# Adafruit_MONSTER_M4SK.net
KiCad netlist of a schematic drawn in EAGLE
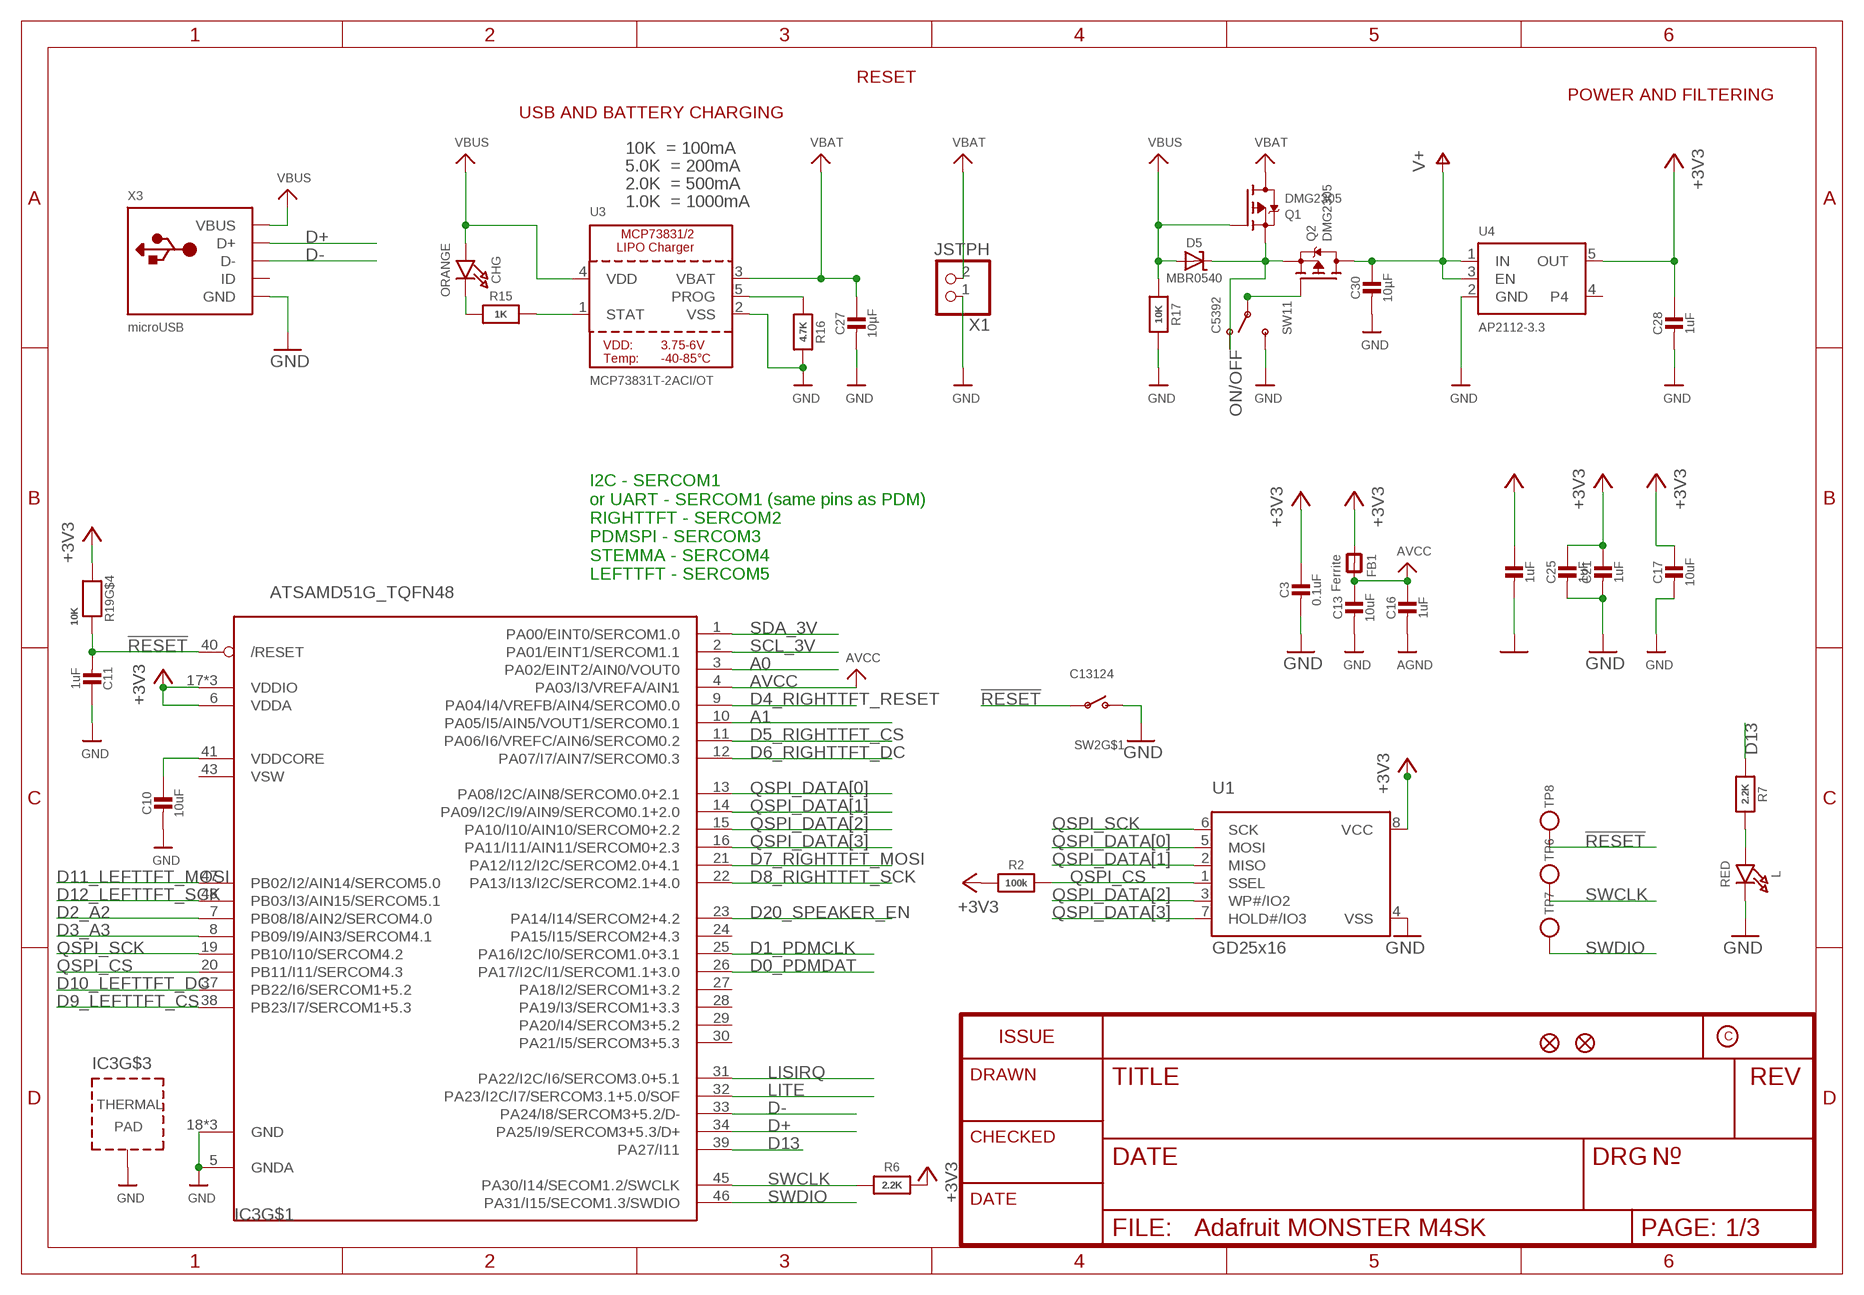
[diagram p0: schematic, sheet 1]
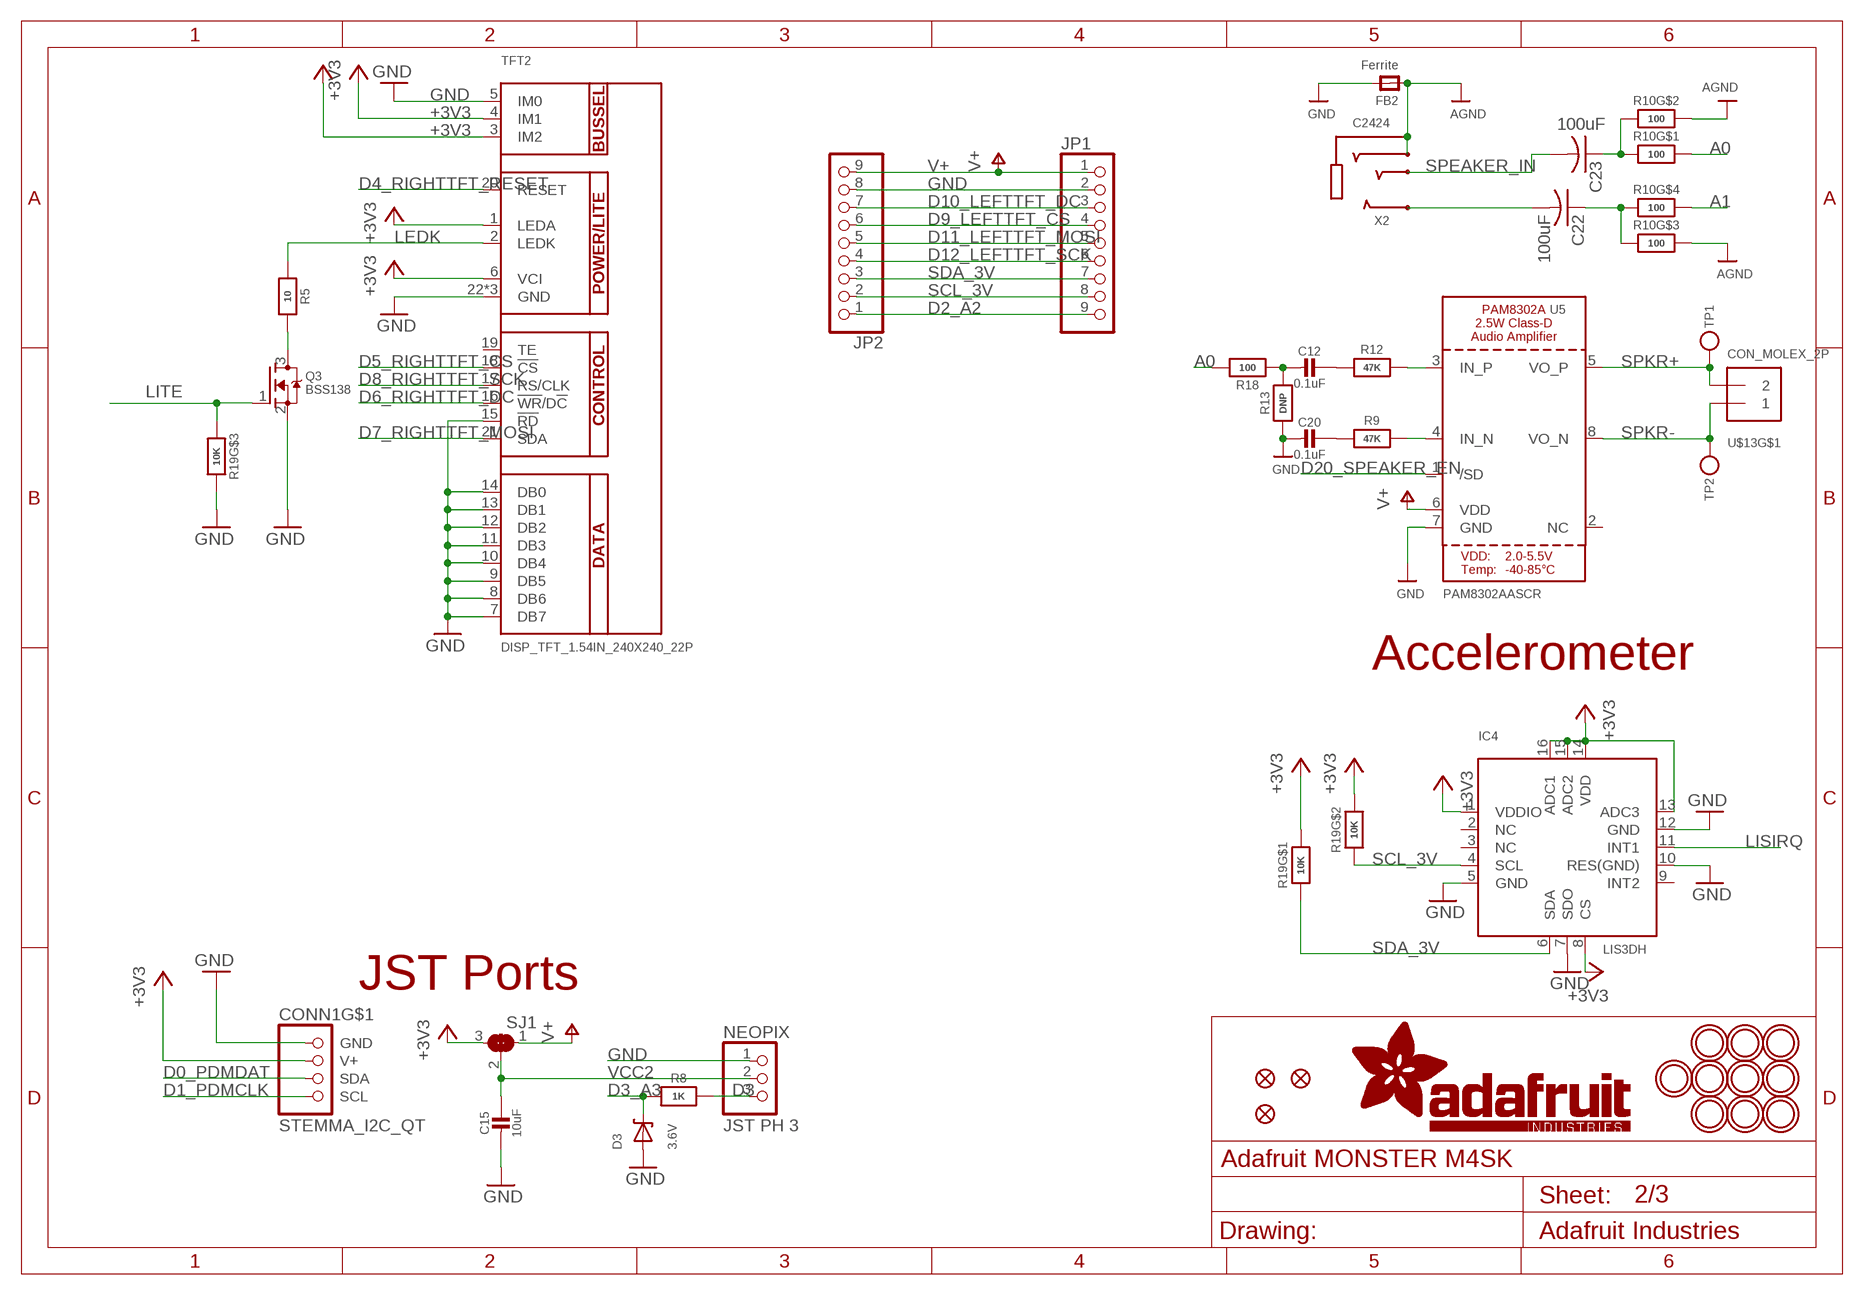
[diagram p1: schematic, sheet 2]
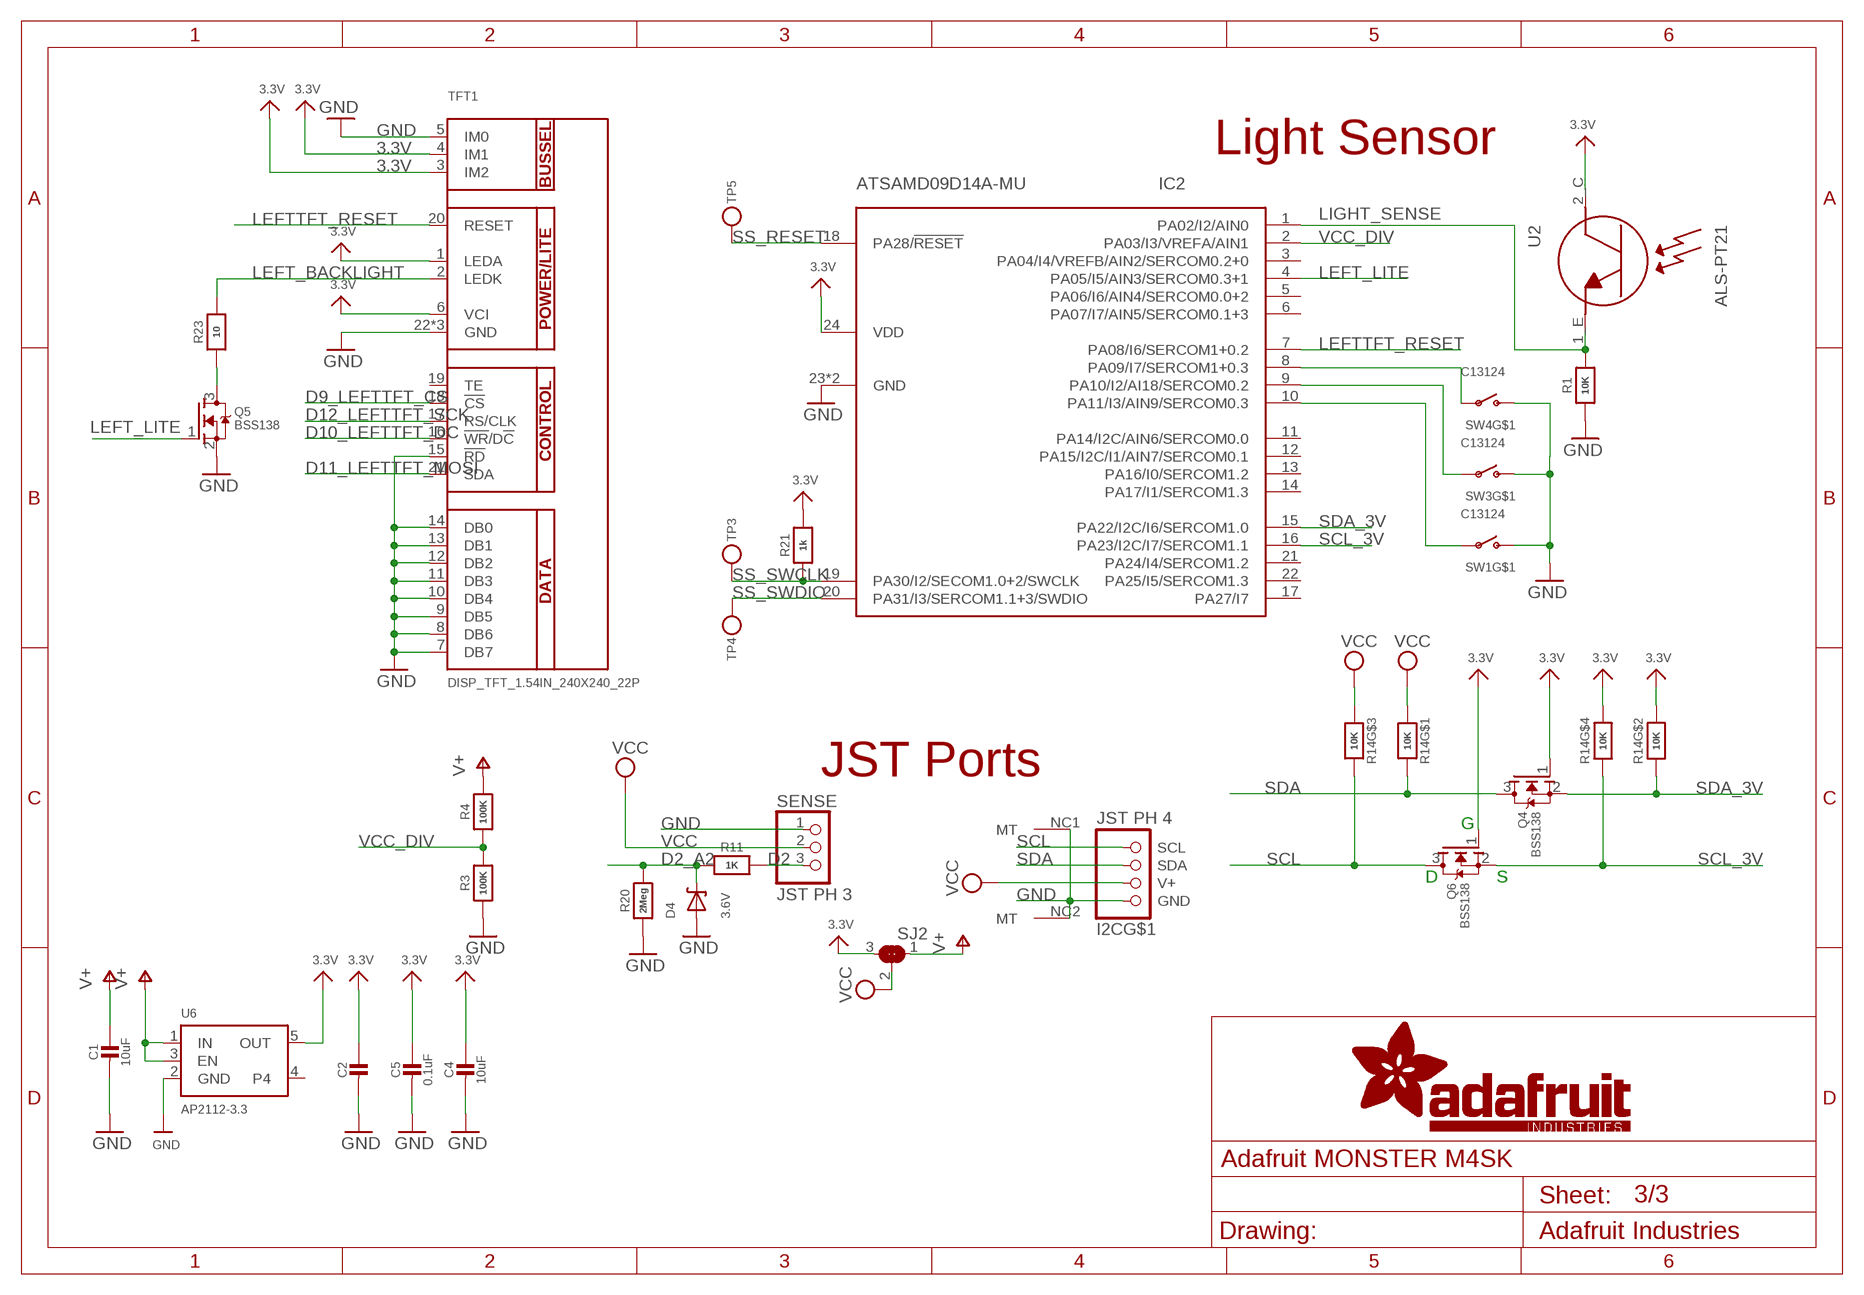
[diagram p2: schematic, sheet 3]

(export (version "E")
  (design (tool "Eeschema 10.0.6"))
  (components
    (comp (ref "C3")
      (value "0.1uF")
      (footprint "eagle-import:0603-NO")
      (libsource (lib "eagle-import") (part "CAP_CERAMIC0603_NO"))
    )
    (comp (ref "C10")
      (value "10uF")
      (footprint "eagle-import:_0805MP")
      (libsource (lib "eagle-import") (part "CAP_CERAMIC_0805MP"))
    )
    (comp (ref "C11")
      (value "1uF")
      (footprint "eagle-import:0603-NO")
      (libsource (lib "eagle-import") (part "CAP_CERAMIC0603_NO"))
    )
    (comp (ref "C13")
      (value "10uF")
      (footprint "eagle-import:0805-NO")
      (libsource (lib "eagle-import") (part "CAP_CERAMIC0805-NOOUTLINE"))
    )
    (comp (ref "C16")
      (value "1uF")
      (footprint "eagle-import:0603-NO")
      (libsource (lib "eagle-import") (part "CAP_CERAMIC0603_NO"))
    )
    (comp (ref "C17")
      (value "10uF")
      (footprint "eagle-import:0805-NO")
      (libsource (lib "eagle-import") (part "CAP_CERAMIC0805-NOOUTLINE"))
    )
    (comp (ref "C19")
      (value "1uF")
      (footprint "eagle-import:0603-NO")
      (libsource (lib "eagle-import") (part "CAP_CERAMIC0603_NO"))
    )
    (comp (ref "C21")
      (value "1uF")
      (footprint "eagle-import:0603-NO")
      (libsource (lib "eagle-import") (part "CAP_CERAMIC0603_NO"))
    )
    (comp (ref "C25")
      (value "1uF")
      (footprint "eagle-import:0603-NO")
      (libsource (lib "eagle-import") (part "CAP_CERAMIC0603_NO"))
    )
    (comp (ref "C27")
      (value "10µF")
      (footprint "eagle-import:0805-NO")
      (libsource (lib "eagle-import") (part "CAP_CERAMIC0805-NOOUTLINE"))
    )
    (comp (ref "C28")
      (value "1uF")
      (footprint "eagle-import:0603-NO")
      (libsource (lib "eagle-import") (part "CAP_CERAMIC0603_NO"))
    )
    (comp (ref "C30")
      (value "10µF")
      (footprint "eagle-import:0805-NO")
      (libsource (lib "eagle-import") (part "CAP_CERAMIC0805-NOOUTLINE"))
    )
    (comp (ref "CHG")
      (value "ORANGE")
      (footprint "eagle-import:CHIPLED_0805_NOOUTLINE")
      (libsource (lib "eagle-import") (part "LED0805_NOOUTLINE"))
    )
    (comp (ref "D5")
      (value "MBR0540")
      (footprint "eagle-import:SOD-123")
      (libsource (lib "eagle-import") (part "DIODE-SCHOTTKYSOD-123"))
    )
    (comp (ref "FB1")
      (value "Ferrite")
      (footprint "eagle-import:0805-NO")
      (libsource (lib "eagle-import") (part "FERRITE-0805NO"))
    )
    (comp (ref "IC3")
      (value "ATSAMD51G_TQFN48")
      (footprint "eagle-import:TQFN48_7MM")
      (libsource (lib "eagle-import") (part "ATSAMD51G_TQFN48"))
    )
    (comp (ref "L")
      (value "RED")
      (footprint "eagle-import:CHIPLED_0805_NOOUTLINE")
      (libsource (lib "eagle-import") (part "LED0805_NOOUTLINE"))
    )
    (comp (ref "Q1")
      (value "DMG2305")
      (footprint "eagle-import:SOT23-R")
      (libsource (lib "eagle-import") (part "MOSFET-P"))
    )
    (comp (ref "Q2")
      (value "DMG2305")
      (footprint "eagle-import:SOT23-R")
      (libsource (lib "eagle-import") (part "MOSFET-P"))
    )
    (comp (ref "R2")
      (value "100k")
      (footprint "eagle-import:0603-NO")
      (libsource (lib "eagle-import") (part "RESISTOR_0603_NOOUT"))
    )
    (comp (ref "R6")
      (value "2.2K")
      (footprint "eagle-import:0603-NO")
      (libsource (lib "eagle-import") (part "RESISTOR_0603_NOOUT"))
    )
    (comp (ref "R7")
      (value "2.2K")
      (footprint "eagle-import:0603-NO")
      (libsource (lib "eagle-import") (part "RESISTOR_0603_NOOUT"))
    )
    (comp (ref "R15")
      (value "1K")
      (footprint "eagle-import:0603-NO")
      (libsource (lib "eagle-import") (part "RESISTOR_0603_NOOUT"))
    )
    (comp (ref "R16")
      (value "4.7K")
      (footprint "eagle-import:0603-NO")
      (libsource (lib "eagle-import") (part "RESISTOR_0603_NOOUT"))
    )
    (comp (ref "R17")
      (value "10K")
      (footprint "eagle-import:0603-NO")
      (libsource (lib "eagle-import") (part "RESISTOR_0603_NOOUT"))
    )
    (comp (ref "R19")
      (value "10K")
      (footprint "eagle-import:RESPACK_4X0603")
      (libsource (lib "eagle-import") (part "RESISTOR_4PACK"))
    )
    (comp (ref "SW2")
      (value "C13124")
      (footprint "eagle-import:SPST_TACTILE_RA")
      (libsource (lib "eagle-import") (part "SWITCH_SPST_TACT_RA"))
    )
    (comp (ref "SW11")
      (value "C5392")
      (footprint "eagle-import:SPDT_SMT_SSSS811101")
      (libsource (lib "eagle-import") (part "SWITCH_SPDT"))
    )
    (comp (ref "TP6")
      (value "TESTPOINTROUND2MMNO")
      (footprint "eagle-import:TESTPOINT_ROUND_2MM_NO")
      (libsource (lib "eagle-import") (part "TESTPOINTROUND2MMNO"))
    )
    (comp (ref "TP7")
      (value "TESTPOINTROUND2MMNO")
      (footprint "eagle-import:TESTPOINT_ROUND_2MM_NO")
      (libsource (lib "eagle-import") (part "TESTPOINTROUND2MMNO"))
    )
    (comp (ref "TP8")
      (value "TESTPOINTROUND2MMNO")
      (footprint "eagle-import:TESTPOINT_ROUND_2MM_NO")
      (libsource (lib "eagle-import") (part "TESTPOINTROUND2MMNO"))
    )
    (comp (ref "U$34")
      (value "FIDUCIAL_1MM")
      (footprint "eagle-import:FIDUCIAL_1MM")
      (libsource (lib "eagle-import") (part "FIDUCIAL_1MM"))
    )
    (comp (ref "U$35")
      (value "FIDUCIAL_1MM")
      (footprint "eagle-import:FIDUCIAL_1MM")
      (libsource (lib "eagle-import") (part "FIDUCIAL_1MM"))
    )
    (comp (ref "U1")
      (value "GD25x16")
      (footprint "eagle-import:SOIC8_208MIL")
      (libsource (lib "eagle-import") (part "SPIFLASH_8PIN208MIL"))
    )
    (comp (ref "U3")
      (value "MCP73831T-2ACI/OT")
      (footprint "eagle-import:SOT23-5")
      (libsource (lib "eagle-import") (part "MCP73831/2"))
    )
    (comp (ref "U4")
      (value "AP2112-3.3")
      (footprint "eagle-import:SOT23-5")
      (libsource (lib "eagle-import") (part "VREG_SOT23-5"))
    )
    (comp (ref "X1")
      (value "JSTPH")
      (footprint "eagle-import:JSTPH2")
      (libsource (lib "eagle-import") (part "CON_JST_PH_2PIN"))
    )
    (comp (ref "X3")
      (value "microUSB")
      (footprint "eagle-import:4UCONN_20329_NARROW")
      (libsource (lib "eagle-import") (part "USB_MICRO_NARROW"))
    )
    (comp (ref "C12")
      (value "0.1uF")
      (footprint "eagle-import:0603-NO")
      (libsource (lib "eagle-import") (part "CAP_CERAMIC0603_NO"))
    )
    (comp (ref "C15")
      (value "10uF")
      (footprint "eagle-import:0805-NO")
      (libsource (lib "eagle-import") (part "CAP_CERAMIC0805-NOOUTLINE"))
    )
    (comp (ref "C20")
      (value "0.1uF")
      (footprint "eagle-import:0603-NO")
      (libsource (lib "eagle-import") (part "CAP_CERAMIC0603_NO"))
    )
    (comp (ref "C22")
      (value "100uF")
      (footprint "eagle-import:C1210")
      (libsource (lib "eagle-import") (part "C-USC1210"))
    )
    (comp (ref "C23")
      (value "100uF")
      (footprint "eagle-import:C1210")
      (libsource (lib "eagle-import") (part "C-USC1210"))
    )
    (comp (ref "CONN1")
      (value "STEMMA_I2C_QT")
      (footprint "eagle-import:JST_SH4")
      (libsource (lib "eagle-import") (part "STEMMA_I2C_QT"))
    )
    (comp (ref "D3")
      (value "3.6V")
      (footprint "eagle-import:SOD-323")
      (libsource (lib "eagle-import") (part "DIODE-ZENERSOD323"))
    )
    (comp (ref "FB2")
      (value "Ferrite")
      (footprint "eagle-import:_0805MP")
      (libsource (lib "eagle-import") (part "FERRITE_0805MP"))
    )
    (comp (ref "IC4")
      (value "LIS3DH")
      (footprint "eagle-import:LGA16_3X3MM")
      (libsource (lib "eagle-import") (part "ACCEL_LIS3DHTR"))
    )
    (comp (ref "JP1")
      (value "HEADER-1X9_JSTSH")
      (footprint "eagle-import:JST_SH9")
      (libsource (lib "eagle-import") (part "HEADER-1X9_JSTSH"))
    )
    (comp (ref "JP2")
      (value "HEADER-1X9_JSTSH")
      (footprint "eagle-import:JST_SH9")
      (libsource (lib "eagle-import") (part "HEADER-1X9_JSTSH"))
    )
    (comp (ref "NEOPIX")
      (value "JST PH 3")
      (footprint "eagle-import:JSTPH3")
      (libsource (lib "eagle-import") (part "CON_JST_PH_3PIN"))
    )
    (comp (ref "Q3")
      (value "BSS138")
      (footprint "eagle-import:SOT23-WIDE")
      (libsource (lib "eagle-import") (part "MOSFET-NWIDE"))
    )
    (comp (ref "R5")
      (value "10")
      (footprint "eagle-import:0603-NO")
      (libsource (lib "eagle-import") (part "RESISTOR_0603_NOOUT"))
    )
    (comp (ref "R8")
      (value "1K")
      (footprint "eagle-import:0603-NO")
      (libsource (lib "eagle-import") (part "RESISTOR_0603_NOOUT"))
    )
    (comp (ref "R9")
      (value "47K")
      (footprint "eagle-import:0603-NO")
      (libsource (lib "eagle-import") (part "RESISTOR_0603_NOOUT"))
    )
    (comp (ref "R10")
      (value "100")
      (footprint "eagle-import:RESPACK_4X0603")
      (libsource (lib "eagle-import") (part "RESISTOR_4PACK"))
    )
    (comp (ref "R12")
      (value "47K")
      (footprint "eagle-import:0603-NO")
      (libsource (lib "eagle-import") (part "RESISTOR_0603_NOOUT"))
    )
    (comp (ref "R13")
      (value "DNP")
      (footprint "eagle-import:0603-NO")
      (libsource (lib "eagle-import") (part "RESISTOR_0603_NOOUT"))
    )
    (comp (ref "R18")
      (value "100")
      (footprint "eagle-import:0603-NO")
      (libsource (lib "eagle-import") (part "RESISTOR_0603_NOOUT"))
    )
    (comp (ref "SJ1")
      (value "SOLDERJUMPER_2WAY")
      (footprint "eagle-import:SOLDERJUMPER_2WAY_OPEN_NOPASTE")
      (libsource (lib "eagle-import") (part "SOLDERJUMPER_2WAY"))
    )
    (comp (ref "TFT2")
      (value "DISP_TFT_1.54IN_240X240_22P")
      (footprint "eagle-import:TFT_1.54IN_240X240_22PIN")
      (libsource (lib "eagle-import") (part "DISP_TFT_1.54IN_240X240_22P"))
    )
    (comp (ref "TP1")
      (value "TESTPOINTROUND1.5MMNO")
      (footprint "eagle-import:TESTPOINT_ROUND_1.5MM_NO")
      (libsource (lib "eagle-import") (part "TESTPOINTROUND1.5MMNO"))
    )
    (comp (ref "TP2")
      (value "TESTPOINTROUND1.5MMNO")
      (footprint "eagle-import:TESTPOINT_ROUND_1.5MM_NO")
      (libsource (lib "eagle-import") (part "TESTPOINTROUND1.5MMNO"))
    )
    (comp (ref "U$3")
      (value "FIDUCIAL_1MM")
      (footprint "eagle-import:FIDUCIAL_1MM")
      (libsource (lib "eagle-import") (part "FIDUCIAL_1MM"))
    )
    (comp (ref "U$4")
      (value "FIDUCIAL_1MM")
      (footprint "eagle-import:FIDUCIAL_1MM")
      (libsource (lib "eagle-import") (part "FIDUCIAL_1MM"))
    )
    (comp (ref "U$5")
      (value "FIDUCIAL_1MM")
      (footprint "eagle-import:FIDUCIAL_1MM")
      (libsource (lib "eagle-import") (part "FIDUCIAL_1MM"))
    )
    (comp (ref "U$7")
      (value "MOUNTINGHOLE3.0THIN")
      (footprint "eagle-import:MOUNTINGHOLE_3.0_PLATEDTHIN")
      (libsource (lib "eagle-import") (part "MOUNTINGHOLE3.0THIN"))
    )
    (comp (ref "U$8")
      (value "MOUNTINGHOLE3.0THIN")
      (footprint "eagle-import:MOUNTINGHOLE_3.0_PLATEDTHIN")
      (libsource (lib "eagle-import") (part "MOUNTINGHOLE3.0THIN"))
    )
    (comp (ref "U$9")
      (value "MOUNTINGHOLE3.0THIN")
      (footprint "eagle-import:MOUNTINGHOLE_3.0_PLATEDTHIN")
      (libsource (lib "eagle-import") (part "MOUNTINGHOLE3.0THIN"))
    )
    (comp (ref "U$10")
      (value "MOUNTINGHOLE3.0THIN")
      (footprint "eagle-import:MOUNTINGHOLE_3.0_PLATEDTHIN")
      (libsource (lib "eagle-import") (part "MOUNTINGHOLE3.0THIN"))
    )
    (comp (ref "U$13")
      (value "CON_MOLEX_2P")
      (footprint "eagle-import:53398-0271")
      (libsource (lib "eagle-import") (part "CON_MOLEX_2P"))
    )
    (comp (ref "U$58")
      (value "MOUNTINGHOLE3.0THIN")
      (footprint "eagle-import:MOUNTINGHOLE_3.0_PLATEDTHIN")
      (libsource (lib "eagle-import") (part "MOUNTINGHOLE3.0THIN"))
    )
    (comp (ref "U$59")
      (value "MOUNTINGHOLE3.0THIN")
      (footprint "eagle-import:MOUNTINGHOLE_3.0_PLATEDTHIN")
      (libsource (lib "eagle-import") (part "MOUNTINGHOLE3.0THIN"))
    )
    (comp (ref "U$60")
      (value "MOUNTINGHOLE3.0THIN")
      (footprint "eagle-import:MOUNTINGHOLE_3.0_PLATEDTHIN")
      (libsource (lib "eagle-import") (part "MOUNTINGHOLE3.0THIN"))
    )
    (comp (ref "U$61")
      (value "MOUNTINGHOLE3.0THIN")
      (footprint "eagle-import:MOUNTINGHOLE_3.0_PLATEDTHIN")
      (libsource (lib "eagle-import") (part "MOUNTINGHOLE3.0THIN"))
    )
    (comp (ref "U$63")
      (value "MOUNTINGHOLE3.0THIN")
      (footprint "eagle-import:MOUNTINGHOLE_3.0_PLATEDTHIN")
      (libsource (lib "eagle-import") (part "MOUNTINGHOLE3.0THIN"))
    )
    (comp (ref "U$64")
      (value "MOUNTINGHOLE3.0THIN")
      (footprint "eagle-import:MOUNTINGHOLE_3.0_PLATEDTHIN")
      (libsource (lib "eagle-import") (part "MOUNTINGHOLE3.0THIN"))
    )
    (comp (ref "U5")
      (value "PAM8302AASCR")
      (footprint "eagle-import:MSOP8_0.65MM")
      (libsource (lib "eagle-import") (part "AUDIOAMP_PAM8302A"))
    )
    (comp (ref "X2")
      (value "C2424")
      (footprint "eagle-import:4UCONN_18510")
      (libsource (lib "eagle-import") (part "AUDIO_3.5MMJACK_4POL"))
    )
    (comp (ref "C1")
      (value "10uF")
      (footprint "eagle-import:0805-NO")
      (libsource (lib "eagle-import") (part "CAP_CERAMIC0805-NOOUTLINE"))
    )
    (comp (ref "C2")
      (value "10uF")
      (footprint "eagle-import:0805-NO")
      (libsource (lib "eagle-import") (part "CAP_CERAMIC0805-NOOUTLINE"))
    )
    (comp (ref "C4")
      (value "10uF")
      (footprint "eagle-import:0805-NO")
      (libsource (lib "eagle-import") (part "CAP_CERAMIC0805-NOOUTLINE"))
    )
    (comp (ref "C5")
      (value "0.1uF")
      (footprint "eagle-import:0603-NO")
      (libsource (lib "eagle-import") (part "CAP_CERAMIC0603_NO"))
    )
    (comp (ref "D4")
      (value "3.6V")
      (footprint "eagle-import:SOD-323")
      (libsource (lib "eagle-import") (part "DIODE-ZENERSOD323"))
    )
    (comp (ref "I2C")
      (value "JST PH 4")
      (footprint "eagle-import:JSTPH4")
      (libsource (lib "eagle-import") (part "STEMMA_I2C_RASMT"))
    )
    (comp (ref "IC2")
      (value "ATSAMD09D14A-MU")
      (footprint "eagle-import:QFN24_4MM")
      (libsource (lib "eagle-import") (part "ATSAMD09D14A-MU"))
    )
    (comp (ref "Q4")
      (value "BSS138")
      (footprint "eagle-import:SOT23-WIDE")
      (libsource (lib "eagle-import") (part "MOSFET-NWIDE"))
    )
    (comp (ref "Q5")
      (value "BSS138")
      (footprint "eagle-import:SOT23-WIDE")
      (libsource (lib "eagle-import") (part "MOSFET-NWIDE"))
    )
    (comp (ref "Q6")
      (value "BSS138")
      (footprint "eagle-import:SOT23-WIDE")
      (libsource (lib "eagle-import") (part "MOSFET-NWIDE"))
    )
    (comp (ref "R1")
      (value "10K")
      (footprint "eagle-import:0603-NO")
      (libsource (lib "eagle-import") (part "RESISTOR_0603_NOOUT"))
    )
    (comp (ref "R3")
      (value "100K")
      (footprint "eagle-import:0603-NO")
      (libsource (lib "eagle-import") (part "RESISTOR_0603_NOOUT"))
    )
    (comp (ref "R4")
      (value "100K")
      (footprint "eagle-import:0603-NO")
      (libsource (lib "eagle-import") (part "RESISTOR_0603_NOOUT"))
    )
    (comp (ref "R11")
      (value "1K")
      (footprint "eagle-import:0603-NO")
      (libsource (lib "eagle-import") (part "RESISTOR_0603_NOOUT"))
    )
    (comp (ref "R14")
      (value "10K")
      (footprint "eagle-import:RESPACK_4X0603")
      (libsource (lib "eagle-import") (part "RESISTOR_4PACK"))
    )
    (comp (ref "R20")
      (value "2Meg")
      (footprint "eagle-import:0603-NO")
      (libsource (lib "eagle-import") (part "RESISTOR_0603_NOOUT"))
    )
    (comp (ref "R21")
      (value "1k")
      (footprint "eagle-import:0603-NO")
      (libsource (lib "eagle-import") (part "RESISTOR_0603_NOOUT"))
    )
    (comp (ref "R23")
      (value "10")
      (footprint "eagle-import:0603-NO")
      (libsource (lib "eagle-import") (part "RESISTOR_0603_NOOUT"))
    )
    (comp (ref "SENSE")
      (value "JST PH 3")
      (footprint "eagle-import:JSTPH3")
      (libsource (lib "eagle-import") (part "CON_JST_PH_3PIN"))
    )
    (comp (ref "SJ2")
      (value "SOLDERJUMPER_2WAY")
      (footprint "eagle-import:SOLDERJUMPER_2WAY_OPEN_NOPASTE")
      (libsource (lib "eagle-import") (part "SOLDERJUMPER_2WAY"))
    )
    (comp (ref "SW1")
      (value "C13124")
      (footprint "eagle-import:SPST_TACTILE_RA")
      (libsource (lib "eagle-import") (part "SWITCH_SPST_TACT_RA"))
    )
    (comp (ref "SW3")
      (value "C13124")
      (footprint "eagle-import:SPST_TACTILE_RA")
      (libsource (lib "eagle-import") (part "SWITCH_SPST_TACT_RA"))
    )
    (comp (ref "SW4")
      (value "C13124")
      (footprint "eagle-import:SPST_TACTILE_RA")
      (libsource (lib "eagle-import") (part "SWITCH_SPST_TACT_RA"))
    )
    (comp (ref "TFT1")
      (value "DISP_TFT_1.54IN_240X240_22P")
      (footprint "eagle-import:TFT_1.54IN_240X240_22PIN")
      (libsource (lib "eagle-import") (part "DISP_TFT_1.54IN_240X240_22P"))
    )
    (comp (ref "TP3")
      (value "TESTPOINTROUND2MM")
      (footprint "eagle-import:TESTPOINT_ROUND_2MM")
      (libsource (lib "eagle-import") (part "TESTPOINTROUND2MM"))
    )
    (comp (ref "TP4")
      (value "TESTPOINTROUND2MM")
      (footprint "eagle-import:TESTPOINT_ROUND_2MM")
      (libsource (lib "eagle-import") (part "TESTPOINTROUND2MM"))
    )
    (comp (ref "TP5")
      (value "TESTPOINTROUND2MM")
      (footprint "eagle-import:TESTPOINT_ROUND_2MM")
      (libsource (lib "eagle-import") (part "TESTPOINTROUND2MM"))
    )
    (comp (ref "U2")
      (value "ALS-PT21")
      (footprint "eagle-import:ALS-PT26-21C")
      (libsource (lib "eagle-import") (part "PHOTOTRANSISTOR_PT26-21C"))
    )
    (comp (ref "U6")
      (value "AP2112-3.3")
      (footprint "eagle-import:SOT23-5")
      (libsource (lib "eagle-import") (part "VREG_SOT23-5"))
    )
  )
  (nets
    (net (code "1") (name "+3V3") (class "Default")
      (node (ref "C17") (pin "1") (pinfunction "1_1") (pintype "passive"))
      (node (ref "C19") (pin "1") (pinfunction "1_1") (pintype "passive"))
      (node (ref "C21") (pin "1") (pinfunction "1_1") (pintype "passive"))
      (node (ref "C25") (pin "1") (pinfunction "1_1") (pintype "passive"))
      (node (ref "C28") (pin "1") (pinfunction "1_1") (pintype "passive"))
      (node (ref "C3") (pin "1") (pinfunction "1_1") (pintype "passive"))
      (node (ref "CONN1") (pin "2") (pinfunction "V+_2") (pintype "passive"))
      (node (ref "FB1") (pin "1") (pinfunction "P$1_1") (pintype "passive"))
      (node (ref "IC3") (pin "17") (pinfunction "VDDIO_17") (pintype "power_in"))
      (node (ref "IC3") (pin "36") (pinfunction "VDDIO_36") (pintype "power_in"))
      (node (ref "IC3") (pin "44") (pinfunction "VDDIO_44") (pintype "power_in"))
      (node (ref "IC3") (pin "6") (pinfunction "VDDA_6") (pintype "power_in"))
      (node (ref "IC4") (pin "1") (pinfunction "VDDIO_1") (pintype "power_in"))
      (node (ref "IC4") (pin "13") (pinfunction "ADC3_13") (pintype "input"))
      (node (ref "IC4") (pin "14") (pinfunction "VDD_14") (pintype "power_in"))
      (node (ref "IC4") (pin "15") (pinfunction "ADC2_15") (pintype "input"))
      (node (ref "IC4") (pin "16") (pinfunction "ADC1_16") (pintype "input"))
      (node (ref "IC4") (pin "8") (pinfunction "CS_8") (pintype "input"))
      (node (ref "R19") (pin "1") (pinfunction "1_1") (pintype "passive"))
      (node (ref "R19") (pin "2") (pinfunction "1_2") (pintype "passive"))
      (node (ref "R19") (pin "4") (pinfunction "1_4") (pintype "passive"))
      (node (ref "R2") (pin "1") (pinfunction "1_1") (pintype "passive"))
      (node (ref "R6") (pin "2") (pinfunction "2_2") (pintype "passive"))
      (node (ref "SJ1") (pin "3") (pinfunction "3_3") (pintype "passive"))
      (node (ref "TFT2") (pin "1") (pinfunction "LEDA_1") (pintype "input"))
      (node (ref "TFT2") (pin "3") (pinfunction "IM2_3") (pintype "input"))
      (node (ref "TFT2") (pin "4") (pinfunction "IM1_4") (pintype "input"))
      (node (ref "TFT2") (pin "6") (pinfunction "VCI_6") (pintype "power_in"))
      (node (ref "U1") (pin "8") (pinfunction "VCC_8") (pintype "bidirectional"))
      (node (ref "U4") (pin "5") (pinfunction "OUT_5") (pintype "power_in"))
    )
    (net (code "2") (name "3.3V") (class "Default")
      (node (ref "C2") (pin "1") (pinfunction "1_1") (pintype "passive"))
      (node (ref "C4") (pin "1") (pinfunction "1_1") (pintype "passive"))
      (node (ref "C5") (pin "1") (pinfunction "1_1") (pintype "passive"))
      (node (ref "IC2") (pin "24") (pinfunction "VDD_24") (pintype "power_in"))
      (node (ref "Q4") (pin "1") (pinfunction "G_1") (pintype "bidirectional"))
      (node (ref "Q6") (pin "1") (pinfunction "G_1") (pintype "bidirectional"))
      (node (ref "R14") (pin "2") (pinfunction "1_2") (pintype "passive"))
      (node (ref "R14") (pin "4") (pinfunction "1_4") (pintype "passive"))
      (node (ref "R21") (pin "2") (pinfunction "2_2") (pintype "passive"))
      (node (ref "SJ2") (pin "3") (pinfunction "3_3") (pintype "passive"))
      (node (ref "TFT1") (pin "1") (pinfunction "LEDA_1") (pintype "input"))
      (node (ref "TFT1") (pin "3") (pinfunction "IM2_3") (pintype "input"))
      (node (ref "TFT1") (pin "4") (pinfunction "IM1_4") (pintype "input"))
      (node (ref "TFT1") (pin "6") (pinfunction "VCI_6") (pintype "power_in"))
      (node (ref "U2") (pin "2_C") (pinfunction "C_2_C") (pintype "bidirectional"))
      (node (ref "U6") (pin "5") (pinfunction "OUT_5") (pintype "power_in"))
    )
    (net (code "3") (name "A0") (class "Default")
      (node (ref "IC3") (pin "3") (pinfunction "PA02/EINT2/AIN0/VOUT0_3") (pintype "bidirectional"))
      (node (ref "R10") (pin "8") (pinfunction "2_8") (pintype "passive"))
      (node (ref "R18") (pin "2") (pinfunction "2_2") (pintype "passive"))
    )
    (net (code "4") (name "A1") (class "Default")
      (node (ref "IC3") (pin "10") (pinfunction "PA05/I5/AIN5/VOUT1/SERCOM0.1_10") (pintype "bidirectional"))
      (node (ref "R10") (pin "5") (pinfunction "2_5") (pintype "passive"))
    )
    (net (code "5") (name "AGND") (class "Default")
      (node (ref "C16") (pin "2") (pinfunction "2_2") (pintype "passive"))
      (node (ref "FB2") (pin "1") (pinfunction "P$1_1") (pintype "passive"))
      (node (ref "R10") (pin "6") (pinfunction "2_6") (pintype "passive"))
      (node (ref "R10") (pin "7") (pinfunction "2_7") (pintype "passive"))
      (node (ref "X2") (pin "1-GND") (pinfunction "TIP_1-GND") (pintype "passive"))
      (node (ref "X2") (pin "4-INNER_SLEEVE") (pinfunction "RING1_4-INNER_SLEEVE") (pintype "passive"))
    )
    (net (code "6") (name "AVCC") (class "Default")
      (node (ref "C13") (pin "1") (pinfunction "1_1") (pintype "passive"))
      (node (ref "C16") (pin "1") (pinfunction "1_1") (pintype "passive"))
      (node (ref "FB1") (pin "2") (pinfunction "P$2_2") (pintype "passive"))
      (node (ref "IC3") (pin "4") (pinfunction "PA03/I3/VREFA/AIN1_4") (pintype "bidirectional"))
    )
    (net (code "7") (name "D+") (class "Default")
      (node (ref "IC3") (pin "34") (pinfunction "PA25/I9/SERCOM3+5.3/D+_34") (pintype "bidirectional"))
      (node (ref "X3") (pin "D+") (pinfunction "D+_D+") (pintype "bidirectional"))
    )
    (net (code "8") (name "D-") (class "Default")
      (node (ref "IC3") (pin "33") (pinfunction "PA24/I8/SERCOM3+5.2/D-_33") (pintype "bidirectional"))
      (node (ref "X3") (pin "D-") (pinfunction "D-_D-") (pintype "bidirectional"))
    )
    (net (code "9") (name "D0_PDMDAT") (class "Default")
      (node (ref "CONN1") (pin "3") (pinfunction "SDA_3") (pintype "passive"))
      (node (ref "IC3") (pin "26") (pinfunction "PA17/I2C/I1/SERCOM1.1+3.0_26") (pintype "bidirectional"))
    )
    (net (code "10") (name "D1_PDMCLK") (class "Default")
      (node (ref "CONN1") (pin "4") (pinfunction "SCL_4") (pintype "passive"))
      (node (ref "IC3") (pin "25") (pinfunction "PA16/I2C/I0/SERCOM1.0+3.1_25") (pintype "bidirectional"))
    )
    (net (code "11") (name "D2") (class "Default")
      (node (ref "R11") (pin "1") (pinfunction "1_1") (pintype "passive"))
      (node (ref "SENSE") (pin "3") (pinfunction "3_3") (pintype "passive"))
    )
    (net (code "12") (name "D2_A2") (class "Default")
      (node (ref "D4") (pin "C") (pinfunction "C_C") (pintype "passive"))
      (node (ref "IC3") (pin "7") (pinfunction "PB08/I8/AIN2/SERCOM4.0_7") (pintype "bidirectional"))
      (node (ref "JP1") (pin "9") (pinfunction "9_9") (pintype "passive"))
      (node (ref "JP2") (pin "1") (pinfunction "1_1") (pintype "passive"))
      (node (ref "R11") (pin "2") (pinfunction "2_2") (pintype "passive"))
      (node (ref "R20") (pin "2") (pinfunction "2_2") (pintype "passive"))
    )
    (net (code "13") (name "D3") (class "Default")
      (node (ref "NEOPIX") (pin "3") (pinfunction "3_3") (pintype "passive"))
      (node (ref "R8") (pin "1") (pinfunction "1_1") (pintype "passive"))
    )
    (net (code "14") (name "D3_A3") (class "Default")
      (node (ref "D3") (pin "C") (pinfunction "C_C") (pintype "passive"))
      (node (ref "IC3") (pin "8") (pinfunction "PB09/I9/AIN3/SERCOM4.1_8") (pintype "bidirectional"))
      (node (ref "R8") (pin "2") (pinfunction "2_2") (pintype "passive"))
    )
    (net (code "15") (name "D4_RIGHTTFT_RESET") (class "Default")
      (node (ref "IC3") (pin "9") (pinfunction "PA04/I4/VREFB/AIN4/SERCOM0.0_9") (pintype "bidirectional"))
      (node (ref "TFT2") (pin "20") (pinfunction "RESET_20") (pintype "input"))
    )
    (net (code "16") (name "D5_RIGHTTFT_CS") (class "Default")
      (node (ref "IC3") (pin "11") (pinfunction "PA06/I6/VREFC/AIN6/SERCOM0.2_11") (pintype "bidirectional"))
      (node (ref "TFT2") (pin "18") (pinfunction "~{CS}_18") (pintype "input"))
    )
    (net (code "17") (name "D6_RIGHTTFT_DC") (class "Default")
      (node (ref "IC3") (pin "12") (pinfunction "PA07/I7/AIN7/SERCOM0.3_12") (pintype "bidirectional"))
      (node (ref "TFT2") (pin "16") (pinfunction "~{WR}/D~{C}_16") (pintype "input"))
    )
    (net (code "18") (name "D7_RIGHTTFT_MOSI") (class "Default")
      (node (ref "IC3") (pin "21") (pinfunction "PA12/I12/I2C/SERCOM2.0+4.1_21") (pintype "bidirectional"))
      (node (ref "TFT2") (pin "21") (pinfunction "SDA_21") (pintype "bidirectional"))
    )
    (net (code "19") (name "D8_RIGHTTFT_SCK") (class "Default")
      (node (ref "IC3") (pin "22") (pinfunction "PA13/I13/I2C/SERCOM2.1+4.0_22") (pintype "bidirectional"))
      (node (ref "TFT2") (pin "17") (pinfunction "RS/CLK_17") (pintype "input"))
    )
    (net (code "20") (name "D9_LEFTTFT_CS") (class "Default")
      (node (ref "IC3") (pin "38") (pinfunction "PB23/I7/SERCOM1+5.3_38") (pintype "bidirectional"))
      (node (ref "JP1") (pin "4") (pinfunction "4_4") (pintype "passive"))
      (node (ref "JP2") (pin "6") (pinfunction "6_6") (pintype "passive"))
      (node (ref "TFT1") (pin "18") (pinfunction "~{CS}_18") (pintype "input"))
    )
    (net (code "21") (name "D10_LEFTTFT_DC") (class "Default")
      (node (ref "IC3") (pin "37") (pinfunction "PB22/I6/SERCOM1+5.2_37") (pintype "bidirectional"))
      (node (ref "JP1") (pin "3") (pinfunction "3_3") (pintype "passive"))
      (node (ref "JP2") (pin "7") (pinfunction "7_7") (pintype "passive"))
      (node (ref "TFT1") (pin "16") (pinfunction "~{WR}/D~{C}_16") (pintype "input"))
    )
    (net (code "22") (name "D11_LEFTTFT_MOSI") (class "Default")
      (node (ref "IC3") (pin "47") (pinfunction "PB02/I2/AIN14/SERCOM5.0_47") (pintype "bidirectional"))
      (node (ref "JP1") (pin "5") (pinfunction "5_5") (pintype "passive"))
      (node (ref "JP2") (pin "5") (pinfunction "5_5") (pintype "passive"))
      (node (ref "TFT1") (pin "21") (pinfunction "SDA_21") (pintype "bidirectional"))
    )
    (net (code "23") (name "D12_LEFTTFT_SCK") (class "Default")
      (node (ref "IC3") (pin "48") (pinfunction "PB03/I3/AIN15/SERCOM5.1_48") (pintype "bidirectional"))
      (node (ref "JP1") (pin "6") (pinfunction "6_6") (pintype "passive"))
      (node (ref "JP2") (pin "4") (pinfunction "4_4") (pintype "passive"))
      (node (ref "TFT1") (pin "17") (pinfunction "RS/CLK_17") (pintype "input"))
    )
    (net (code "24") (name "D13") (class "Default")
      (node (ref "IC3") (pin "39") (pinfunction "PA27/I11_39") (pintype "bidirectional"))
      (node (ref "R7") (pin "1") (pinfunction "1_1") (pintype "passive"))
    )
    (net (code "25") (name "D20_SPEAKER_EN") (class "Default")
      (node (ref "IC3") (pin "23") (pinfunction "PA14/I14/SERCOM2+4.2_23") (pintype "bidirectional"))
      (node (ref "U5") (pin "1") (pinfunction "/SD_1") (pintype "input"))
    )
    (net (code "26") (name "GND") (class "Default")
      (node (ref "C1") (pin "2") (pinfunction "2_2") (pintype "passive"))
      (node (ref "C10") (pin "2") (pinfunction "2_2") (pintype "passive"))
      (node (ref "C11") (pin "1") (pinfunction "1_1") (pintype "passive"))
      (node (ref "C13") (pin "2") (pinfunction "2_2") (pintype "passive"))
      (node (ref "C15") (pin "2") (pinfunction "2_2") (pintype "passive"))
      (node (ref "C17") (pin "2") (pinfunction "2_2") (pintype "passive"))
      (node (ref "C19") (pin "2") (pinfunction "2_2") (pintype "passive"))
      (node (ref "C2") (pin "2") (pinfunction "2_2") (pintype "passive"))
      (node (ref "C20") (pin "2") (pinfunction "2_2") (pintype "passive"))
      (node (ref "C21") (pin "2") (pinfunction "2_2") (pintype "passive"))
      (node (ref "C25") (pin "2") (pinfunction "2_2") (pintype "passive"))
      (node (ref "C27") (pin "2") (pinfunction "2_2") (pintype "passive"))
      (node (ref "C28") (pin "2") (pinfunction "2_2") (pintype "passive"))
      (node (ref "C3") (pin "2") (pinfunction "2_2") (pintype "passive"))
      (node (ref "C30") (pin "2") (pinfunction "2_2") (pintype "passive"))
      (node (ref "C4") (pin "2") (pinfunction "2_2") (pintype "passive"))
      (node (ref "C5") (pin "2") (pinfunction "2_2") (pintype "passive"))
      (node (ref "CONN1") (pin "1") (pinfunction "GND_1") (pintype "passive"))
      (node (ref "D3") (pin "A") (pinfunction "A_A") (pintype "passive"))
      (node (ref "D4") (pin "A") (pinfunction "A_A") (pintype "passive"))
      (node (ref "FB2") (pin "2") (pinfunction "P$2_2") (pintype "passive"))
      (node (ref "I2C") (pin "1") (pinfunction "GND_1") (pintype "passive"))
      (node (ref "I2C") (pin "NC1") (pinfunction "MT_NC1") (pintype "bidirectional"))
      (node (ref "I2C") (pin "NC2") (pinfunction "MT_NC2") (pintype "bidirectional"))
      (node (ref "IC2") (pin "23") (pinfunction "GND_23") (pintype "power_in"))
      (node (ref "IC2") (pin "THERM") (pinfunction "GND_THERM") (pintype "power_in"))
      (node (ref "IC3") (pin "18") (pinfunction "GND_18") (pintype "power_in"))
      (node (ref "IC3") (pin "35") (pinfunction "GND_35") (pintype "power_in"))
      (node (ref "IC3") (pin "42") (pinfunction "GND_42") (pintype "power_in"))
      (node (ref "IC3") (pin "5") (pinfunction "GNDA_5") (pintype "power_in"))
      (node (ref "IC3") (pin "THERMAL") (pinfunction "TP_THERMAL") (pintype "power_in"))
      (node (ref "IC4") (pin "10") (pinfunction "RES(GND)_10") (pintype "bidirectional"))
      (node (ref "IC4") (pin "12") (pinfunction "GND_12") (pintype "power_in"))
      (node (ref "IC4") (pin "5") (pinfunction "GND_5") (pintype "power_in"))
      (node (ref "IC4") (pin "7") (pinfunction "SDO_7") (pintype "bidirectional"))
      (node (ref "JP1") (pin "2") (pinfunction "2_2") (pintype "passive"))
      (node (ref "JP2") (pin "8") (pinfunction "8_8") (pintype "passive"))
      (node (ref "L") (pin "C") (pinfunction "C_C") (pintype "passive"))
      (node (ref "NEOPIX") (pin "1") (pinfunction "1_1") (pintype "passive"))
      (node (ref "Q3") (pin "2") (pinfunction "S_2") (pintype "bidirectional"))
      (node (ref "Q5") (pin "2") (pinfunction "S_2") (pintype "bidirectional"))
      (node (ref "R1") (pin "1") (pinfunction "1_1") (pintype "passive"))
      (node (ref "R13") (pin "1") (pinfunction "1_1") (pintype "passive"))
      (node (ref "R16") (pin "2") (pinfunction "2_2") (pintype "passive"))
      (node (ref "R17") (pin "2") (pinfunction "2_2") (pintype "passive"))
      (node (ref "R19") (pin "3") (pinfunction "1_3") (pintype "passive"))
      (node (ref "R20") (pin "1") (pinfunction "1_1") (pintype "passive"))
      (node (ref "R3") (pin "1") (pinfunction "1_1") (pintype "passive"))
      (node (ref "SENSE") (pin "1") (pinfunction "1_1") (pintype "passive"))
      (node (ref "SW1") (pin "2") (pinfunction "S_2") (pintype "passive"))
      (node (ref "SW11") (pin "C") (pinfunction "S_C") (pintype "passive"))
      (node (ref "SW2") (pin "2") (pinfunction "S_2") (pintype "passive"))
      (node (ref "SW3") (pin "2") (pinfunction "S_2") (pintype "passive"))
      (node (ref "SW4") (pin "2") (pinfunction "S_2") (pintype "passive"))
      (node (ref "TFT1") (pin "10") (pinfunction "DB4_10") (pintype "bidirectional"))
      (node (ref "TFT1") (pin "11") (pinfunction "DB3_11") (pintype "bidirectional"))
      (node (ref "TFT1") (pin "12") (pinfunction "DB2_12") (pintype "bidirectional"))
      (node (ref "TFT1") (pin "13") (pinfunction "DB1_13") (pintype "bidirectional"))
      (node (ref "TFT1") (pin "14") (pinfunction "DB0_14") (pintype "bidirectional"))
      (node (ref "TFT1") (pin "15") (pinfunction "~{RD}_15") (pintype "input"))
      (node (ref "TFT1") (pin "22") (pinfunction "GND_22") (pintype "power_in"))
      (node (ref "TFT1") (pin "5") (pinfunction "IM0_5") (pintype "input"))
      (node (ref "TFT1") (pin "7") (pinfunction "DB7_7") (pintype "bidirectional"))
      (node (ref "TFT1") (pin "8") (pinfunction "DB6_8") (pintype "bidirectional"))
      (node (ref "TFT1") (pin "9") (pinfunction "DB5_9") (pintype "bidirectional"))
      (node (ref "TFT1") (pin "SUPPORT1") (pinfunction "GND_SUPPORT1") (pintype "power_in"))
      (node (ref "TFT1") (pin "SUPPORT2") (pinfunction "GND_SUPPORT2") (pintype "power_in"))
      (node (ref "TFT2") (pin "10") (pinfunction "DB4_10") (pintype "bidirectional"))
      (node (ref "TFT2") (pin "11") (pinfunction "DB3_11") (pintype "bidirectional"))
      (node (ref "TFT2") (pin "12") (pinfunction "DB2_12") (pintype "bidirectional"))
      (node (ref "TFT2") (pin "13") (pinfunction "DB1_13") (pintype "bidirectional"))
      (node (ref "TFT2") (pin "14") (pinfunction "DB0_14") (pintype "bidirectional"))
      (node (ref "TFT2") (pin "15") (pinfunction "~{RD}_15") (pintype "input"))
      (node (ref "TFT2") (pin "22") (pinfunction "GND_22") (pintype "power_in"))
      (node (ref "TFT2") (pin "5") (pinfunction "IM0_5") (pintype "input"))
      (node (ref "TFT2") (pin "7") (pinfunction "DB7_7") (pintype "bidirectional"))
      (node (ref "TFT2") (pin "8") (pinfunction "DB6_8") (pintype "bidirectional"))
      (node (ref "TFT2") (pin "9") (pinfunction "DB5_9") (pintype "bidirectional"))
      (node (ref "TFT2") (pin "SUPPORT1") (pinfunction "GND_SUPPORT1") (pintype "power_in"))
      (node (ref "TFT2") (pin "SUPPORT2") (pinfunction "GND_SUPPORT2") (pintype "power_in"))
      (node (ref "U1") (pin "4") (pinfunction "VSS_4") (pintype "bidirectional"))
      (node (ref "U3") (pin "2") (pinfunction "VSS_2") (pintype "power_in"))
      (node (ref "U4") (pin "2") (pinfunction "GND_2") (pintype "power_in"))
      (node (ref "U5") (pin "7") (pinfunction "GND_7") (pintype "power_in"))
      (node (ref "U6") (pin "2") (pinfunction "GND_2") (pintype "power_in"))
      (node (ref "X1") (pin "1") (pinfunction "1_1") (pintype "passive"))
      (node (ref "X3") (pin "BASE@1") (pinfunction "GND_BASE@1") (pintype "power_in"))
      (node (ref "X3") (pin "BASE@2") (pinfunction "GND_BASE@2") (pintype "power_in"))
      (node (ref "X3") (pin "GND") (pinfunction "GND_GND") (pintype "power_in"))
      (node (ref "X3") (pin "SPRT@1") (pinfunction "GND_SPRT@1") (pintype "power_in"))
      (node (ref "X3") (pin "SPRT@2") (pinfunction "GND_SPRT@2") (pintype "power_in"))
      (node (ref "X3") (pin "SPRT@3") (pinfunction "GND_SPRT@3") (pintype "power_in"))
      (node (ref "X3") (pin "SPRT@4") (pinfunction "GND_SPRT@4") (pintype "power_in"))
    )
    (net (code "27") (name "LEDK") (class "Default")
      (node (ref "R5") (pin "2") (pinfunction "2_2") (pintype "passive"))
      (node (ref "TFT2") (pin "2") (pinfunction "LEDK_2") (pintype "input"))
    )
    (net (code "28") (name "LEFTTFT_RESET") (class "Default")
      (node (ref "IC2") (pin "7") (pinfunction "PA08/I6/SERCOM1+0.2_7") (pintype "bidirectional"))
      (node (ref "TFT1") (pin "20") (pinfunction "RESET_20") (pintype "input"))
    )
    (net (code "29") (name "LEFT_BACKLIGHT") (class "Default")
      (node (ref "R23") (pin "2") (pinfunction "2_2") (pintype "passive"))
      (node (ref "TFT1") (pin "2") (pinfunction "LEDK_2") (pintype "input"))
    )
    (net (code "30") (name "LEFT_LITE") (class "Default")
      (node (ref "IC2") (pin "4") (pinfunction "PA05/I5/AIN3/SERCOM0.3+1_4") (pintype "bidirectional"))
      (node (ref "Q5") (pin "1") (pinfunction "G_1") (pintype "bidirectional"))
    )
    (net (code "31") (name "LIGHT_SENSE") (class "Default")
      (node (ref "IC2") (pin "1") (pinfunction "PA02/I2/AIN0_1") (pintype "bidirectional"))
      (node (ref "R1") (pin "2") (pinfunction "2_2") (pintype "passive"))
      (node (ref "U2") (pin "1_E") (pinfunction "E_1_E") (pintype "bidirectional"))
    )
    (net (code "32") (name "LISIRQ") (class "Default")
      (node (ref "IC3") (pin "31") (pinfunction "PA22/I2C/I6/SERCOM3.0+5.1_31") (pintype "bidirectional"))
      (node (ref "IC4") (pin "11") (pinfunction "INT1_11") (pintype "output"))
    )
    (net (code "33") (name "LITE") (class "Default")
      (node (ref "IC3") (pin "32") (pinfunction "PA23/I2C/I7/SERCOM3.1+5.0/SOF_32") (pintype "bidirectional"))
      (node (ref "Q3") (pin "1") (pinfunction "G_1") (pintype "bidirectional"))
      (node (ref "R19") (pin "6") (pinfunction "2_6") (pintype "passive"))
    )
    (net (code "34") (name "Net-(C12-Pad1)") (class "Default")
      (node (ref "C12") (pin "1") (pinfunction "1_1") (pintype "passive"))
      (node (ref "R12") (pin "1") (pinfunction "1_1") (pintype "passive"))
    )
    (net (code "35") (name "Net-(C12-Pad2)") (class "Default")
      (node (ref "C12") (pin "2") (pinfunction "2_2") (pintype "passive"))
      (node (ref "R13") (pin "2") (pinfunction "2_2") (pintype "passive"))
      (node (ref "R18") (pin "1") (pinfunction "1_1") (pintype "passive"))
    )
    (net (code "36") (name "Net-(C20-Pad1)") (class "Default")
      (node (ref "C20") (pin "1") (pinfunction "1_1") (pintype "passive"))
      (node (ref "R9") (pin "1") (pinfunction "1_1") (pintype "passive"))
    )
    (net (code "37") (name "Net-(CHG-PadC)") (class "Default")
      (node (ref "CHG") (pin "C") (pinfunction "C_C") (pintype "passive"))
      (node (ref "R15") (pin "1") (pinfunction "1_1") (pintype "passive"))
    )
    (net (code "38") (name "Net-(IC2-PA09{slash}I7{slash}SERCOM1+0.3)") (class "Default")
      (node (ref "IC2") (pin "8") (pinfunction "PA09/I7/SERCOM1+0.3_8") (pintype "bidirectional"))
      (node (ref "SW4") (pin "1") (pinfunction "P_1") (pintype "passive"))
    )
    (net (code "39") (name "Net-(IC2-PA10{slash}I2{slash}AI18{slash}SERCOM0.2)") (class "Default")
      (node (ref "IC2") (pin "9") (pinfunction "PA10/I2/AI18/SERCOM0.2_9") (pintype "bidirectional"))
      (node (ref "SW3") (pin "1") (pinfunction "P_1") (pintype "passive"))
    )
    (net (code "40") (name "Net-(IC2-PA11{slash}I3{slash}AIN9{slash}SERCOM0.3)") (class "Default")
      (node (ref "IC2") (pin "10") (pinfunction "PA11/I3/AIN9/SERCOM0.3_10") (pintype "bidirectional"))
      (node (ref "SW1") (pin "1") (pinfunction "P_1") (pintype "passive"))
    )
    (net (code "41") (name "Net-(IC3A-VDDCORE)") (class "Default")
      (node (ref "C10") (pin "1") (pinfunction "1_1") (pintype "passive"))
      (node (ref "IC3") (pin "41") (pinfunction "VDDCORE_41") (pintype "power_in"))
    )
    (net (code "42") (name "Net-(L-PadA)") (class "Default")
      (node (ref "L") (pin "A") (pinfunction "A_A") (pintype "passive"))
      (node (ref "R7") (pin "2") (pinfunction "2_2") (pintype "passive"))
    )
    (net (code "43") (name "Net-(Q1-S)") (class "Default")
      (node (ref "D5") (pin "C") (pinfunction "C_C") (pintype "passive"))
      (node (ref "Q1") (pin "2") (pinfunction "S_2") (pintype "passive"))
      (node (ref "Q2") (pin "2") (pinfunction "S_2") (pintype "passive"))
      (node (ref "SW11") (pin "A") (pinfunction "O_A") (pintype "passive"))
    )
    (net (code "44") (name "Net-(Q3-D)") (class "Default")
      (node (ref "Q3") (pin "3") (pinfunction "D_3") (pintype "bidirectional"))
      (node (ref "R5") (pin "1") (pinfunction "1_1") (pintype "passive"))
    )
    (net (code "45") (name "Net-(Q5-D)") (class "Default")
      (node (ref "Q5") (pin "3") (pinfunction "D_3") (pintype "bidirectional"))
      (node (ref "R23") (pin "1") (pinfunction "1_1") (pintype "passive"))
    )
    (net (code "46") (name "Net-(R10B-1)") (class "Default")
      (node (ref "C23") (pin "1") (pinfunction "1_1") (pintype "passive"))
      (node (ref "R10") (pin "1") (pinfunction "1_1") (pintype "passive"))
      (node (ref "R10") (pin "2") (pinfunction "1_2") (pintype "passive"))
    )
    (net (code "47") (name "Net-(R10C-1)") (class "Default")
      (node (ref "C22") (pin "1") (pinfunction "1_1") (pintype "passive"))
      (node (ref "R10") (pin "3") (pinfunction "1_3") (pintype "passive"))
      (node (ref "R10") (pin "4") (pinfunction "1_4") (pintype "passive"))
    )
    (net (code "48") (name "Net-(U3-PROG)") (class "Default")
      (node (ref "R16") (pin "1") (pinfunction "1_1") (pintype "passive"))
      (node (ref "U3") (pin "5") (pinfunction "PROG_5") (pintype "input"))
    )
    (net (code "49") (name "Net-(U3-STAT)") (class "Default")
      (node (ref "R15") (pin "2") (pinfunction "2_2") (pintype "passive"))
      (node (ref "U3") (pin "1") (pinfunction "STAT_1") (pintype "output"))
    )
    (net (code "50") (name "Net-(U5-IN_N)") (class "Default")
      (node (ref "R9") (pin "2") (pinfunction "2_2") (pintype "passive"))
      (node (ref "U5") (pin "4") (pinfunction "IN_N_4") (pintype "input"))
    )
    (net (code "51") (name "Net-(U5-IN_P)") (class "Default")
      (node (ref "R12") (pin "2") (pinfunction "2_2") (pintype "passive"))
      (node (ref "U5") (pin "3") (pinfunction "IN_P_3") (pintype "input"))
    )
    (net (code "52") (name "Net-(X2-RING2)") (class "Default")
      (node (ref "C22") (pin "2") (pinfunction "2_2") (pintype "passive"))
      (node (ref "X2") (pin "3-OUTER_SLEEVE") (pinfunction "RING2_3-OUTER_SLEEVE") (pintype "passive"))
    )
    (net (code "53") (name "ON{slash}OFF") (class "Default")
      (node (ref "Q2") (pin "1") (pinfunction "G_1") (pintype "passive"))
      (node (ref "SW11") (pin "B") (pinfunction "P_B") (pintype "passive"))
    )
    (net (code "54") (name "QSPI_CS") (class "Default")
      (node (ref "IC3") (pin "20") (pinfunction "PB11/I11/SERCOM4.3_20") (pintype "bidirectional"))
      (node (ref "R2") (pin "2") (pinfunction "2_2") (pintype "passive"))
      (node (ref "U1") (pin "1") (pinfunction "SSEL_1") (pintype "bidirectional"))
    )
    (net (code "55") (name "QSPI_DATA[0]") (class "Default")
      (node (ref "IC3") (pin "13") (pinfunction "PA08/I2C/AIN8/SERCOM0.0+2.1_13") (pintype "bidirectional"))
      (node (ref "U1") (pin "5") (pinfunction "MOSI_5") (pintype "bidirectional"))
    )
    (net (code "56") (name "QSPI_DATA[1]") (class "Default")
      (node (ref "IC3") (pin "14") (pinfunction "PA09/I2C/I9/AIN9/SERCOM0.1+2.0_14") (pintype "bidirectional"))
      (node (ref "U1") (pin "2") (pinfunction "MISO_2") (pintype "bidirectional"))
    )
    (net (code "57") (name "QSPI_DATA[2]") (class "Default")
      (node (ref "IC3") (pin "15") (pinfunction "PA10/I10/AIN10/SERCOM0+2.2_15") (pintype "bidirectional"))
      (node (ref "U1") (pin "3") (pinfunction "WP#/IO2_3") (pintype "bidirectional"))
    )
    (net (code "58") (name "QSPI_DATA[3]") (class "Default")
      (node (ref "IC3") (pin "16") (pinfunction "PA11/I11/AIN11/SERCOM0+2.3_16") (pintype "bidirectional"))
      (node (ref "U1") (pin "7") (pinfunction "HOLD#/IO3_7") (pintype "bidirectional"))
    )
    (net (code "59") (name "QSPI_SCK") (class "Default")
      (node (ref "IC3") (pin "19") (pinfunction "PB10/I10/SERCOM4.2_19") (pintype "bidirectional"))
      (node (ref "U1") (pin "6") (pinfunction "SCK_6") (pintype "bidirectional"))
    )
    (net (code "60") (name "SCL") (class "Default")
      (node (ref "I2C") (pin "4") (pinfunction "SCL_4") (pintype "passive"))
      (node (ref "Q6") (pin "3") (pinfunction "D_3") (pintype "bidirectional"))
      (node (ref "R14") (pin "6") (pinfunction "2_6") (pintype "passive"))
    )
    (net (code "61") (name "SCL_3V") (class "Default")
      (node (ref "IC2") (pin "16") (pinfunction "PA23/I2C/I7/SERCOM1.1_16") (pintype "bidirectional"))
      (node (ref "IC3") (pin "2") (pinfunction "PA01/EINT1/SERCOM1.1_2") (pintype "bidirectional"))
      (node (ref "IC4") (pin "4") (pinfunction "SCL_4") (pintype "bidirectional"))
      (node (ref "JP1") (pin "8") (pinfunction "8_8") (pintype "passive"))
      (node (ref "JP2") (pin "2") (pinfunction "2_2") (pintype "passive"))
      (node (ref "Q6") (pin "2") (pinfunction "S_2") (pintype "bidirectional"))
      (node (ref "R14") (pin "5") (pinfunction "2_5") (pintype "passive"))
      (node (ref "R19") (pin "7") (pinfunction "2_7") (pintype "passive"))
    )
    (net (code "62") (name "SDA") (class "Default")
      (node (ref "I2C") (pin "3") (pinfunction "SDA_3") (pintype "passive"))
      (node (ref "Q4") (pin "3") (pinfunction "D_3") (pintype "bidirectional"))
      (node (ref "R14") (pin "8") (pinfunction "2_8") (pintype "passive"))
    )
    (net (code "63") (name "SDA_3V") (class "Default")
      (node (ref "IC2") (pin "15") (pinfunction "PA22/I2C/I6/SERCOM1.0_15") (pintype "bidirectional"))
      (node (ref "IC3") (pin "1") (pinfunction "PA00/EINT0/SERCOM1.0_1") (pintype "bidirectional"))
      (node (ref "IC4") (pin "6") (pinfunction "SDA_6") (pintype "bidirectional"))
      (node (ref "JP1") (pin "7") (pinfunction "7_7") (pintype "passive"))
      (node (ref "JP2") (pin "3") (pinfunction "3_3") (pintype "passive"))
      (node (ref "Q4") (pin "2") (pinfunction "S_2") (pintype "bidirectional"))
      (node (ref "R14") (pin "7") (pinfunction "2_7") (pintype "passive"))
      (node (ref "R19") (pin "8") (pinfunction "2_8") (pintype "passive"))
    )
    (net (code "64") (name "SPEAKER_IN") (class "Default")
      (node (ref "C23") (pin "2") (pinfunction "2_2") (pintype "passive"))
      (node (ref "X2") (pin "2-TIP") (pinfunction "RING3_2-TIP") (pintype "passive"))
    )
    (net (code "65") (name "SPKR+") (class "Default")
      (node (ref "TP1") (pin "P$1") (pinfunction "P$1_P$1") (pintype "bidirectional"))
      (node (ref "U$13") (pin "2") (pinfunction "2_2") (pintype "passive"))
      (node (ref "U5") (pin "5") (pinfunction "VO_P_5") (pintype "output"))
    )
    (net (code "66") (name "SPKR-") (class "Default")
      (node (ref "TP2") (pin "P$1") (pinfunction "P$1_P$1") (pintype "bidirectional"))
      (node (ref "U$13") (pin "1") (pinfunction "1_1") (pintype "passive"))
      (node (ref "U5") (pin "8") (pinfunction "VO_N_8") (pintype "output"))
    )
    (net (code "67") (name "SS_RESET") (class "Default")
      (node (ref "IC2") (pin "18") (pinfunction "PA28/~{RESET}_18") (pintype "bidirectional"))
      (node (ref "TP5") (pin "P$1") (pinfunction "P$1_P$1") (pintype "bidirectional"))
    )
    (net (code "68") (name "SS_SWCLK") (class "Default")
      (node (ref "IC2") (pin "19") (pinfunction "PA30/I2/SECOM1.0+2/SWCLK_19") (pintype "bidirectional"))
      (node (ref "R21") (pin "1") (pinfunction "1_1") (pintype "passive"))
      (node (ref "TP3") (pin "P$1") (pinfunction "P$1_P$1") (pintype "bidirectional"))
    )
    (net (code "69") (name "SS_SWDIO") (class "Default")
      (node (ref "IC2") (pin "20") (pinfunction "PA31/I3/SERCOM1.1+3/SWDIO_20") (pintype "bidirectional"))
      (node (ref "TP4") (pin "P$1") (pinfunction "P$1_P$1") (pintype "bidirectional"))
    )
    (net (code "70") (name "SWCLK") (class "Default")
      (node (ref "IC3") (pin "45") (pinfunction "PA30/I14/SECOM1.2/SWCLK_45") (pintype "bidirectional"))
      (node (ref "R6") (pin "1") (pinfunction "1_1") (pintype "passive"))
      (node (ref "TP6") (pin "P$1") (pinfunction "P$1_P$1") (pintype "bidirectional"))
    )
    (net (code "71") (name "SWDIO") (class "Default")
      (node (ref "IC3") (pin "46") (pinfunction "PA31/I15/SECOM1.3/SWDIO_46") (pintype "bidirectional"))
      (node (ref "TP7") (pin "P$1") (pinfunction "P$1_P$1") (pintype "bidirectional"))
    )
    (net (code "72") (name "V+") (class "Default")
      (node (ref "C1") (pin "1") (pinfunction "1_1") (pintype "passive"))
      (node (ref "C30") (pin "1") (pinfunction "1_1") (pintype "passive"))
      (node (ref "JP1") (pin "1") (pinfunction "1_1") (pintype "passive"))
      (node (ref "JP2") (pin "9") (pinfunction "9_9") (pintype "passive"))
      (node (ref "Q2") (pin "3") (pinfunction "D_3") (pintype "passive"))
      (node (ref "R4") (pin "2") (pinfunction "2_2") (pintype "passive"))
      (node (ref "SJ1") (pin "1") (pinfunction "1_1") (pintype "passive"))
      (node (ref "SJ2") (pin "1") (pinfunction "1_1") (pintype "passive"))
      (node (ref "U4") (pin "1") (pinfunction "IN_1") (pintype "power_in"))
      (node (ref "U4") (pin "3") (pinfunction "EN_3") (pintype "input"))
      (node (ref "U5") (pin "6") (pinfunction "VDD_6") (pintype "power_in"))
      (node (ref "U6") (pin "1") (pinfunction "IN_1") (pintype "power_in"))
      (node (ref "U6") (pin "3") (pinfunction "EN_3") (pintype "input"))
    )
    (net (code "73") (name "VBAT") (class "Default")
      (node (ref "C27") (pin "1") (pinfunction "1_1") (pintype "passive"))
      (node (ref "Q1") (pin "3") (pinfunction "D_3") (pintype "passive"))
      (node (ref "U3") (pin "3") (pinfunction "VBAT_3") (pintype "power_in"))
      (node (ref "X1") (pin "2") (pinfunction "2_2") (pintype "passive"))
    )
    (net (code "74") (name "VBUS") (class "Default")
      (node (ref "CHG") (pin "A") (pinfunction "A_A") (pintype "passive"))
      (node (ref "D5") (pin "A") (pinfunction "A_A") (pintype "passive"))
      (node (ref "Q1") (pin "1") (pinfunction "G_1") (pintype "passive"))
      (node (ref "R17") (pin "1") (pinfunction "1_1") (pintype "passive"))
      (node (ref "U3") (pin "4") (pinfunction "VDD_4") (pintype "power_in"))
      (node (ref "X3") (pin "VBUS") (pinfunction "VBUS_VBUS") (pintype "power_in"))
    )
    (net (code "75") (name "VCC") (class "Default")
      (node (ref "I2C") (pin "2") (pinfunction "V+_2") (pintype "passive"))
      (node (ref "R14") (pin "1") (pinfunction "1_1") (pintype "passive"))
      (node (ref "R14") (pin "3") (pinfunction "1_3") (pintype "passive"))
      (node (ref "SENSE") (pin "2") (pinfunction "2_2") (pintype "passive"))
      (node (ref "SJ2") (pin "2") (pinfunction "2_2") (pintype "passive"))
    )
    (net (code "76") (name "VCC2") (class "Default")
      (node (ref "C15") (pin "1") (pinfunction "1_1") (pintype "passive"))
      (node (ref "NEOPIX") (pin "2") (pinfunction "2_2") (pintype "passive"))
      (node (ref "SJ1") (pin "2") (pinfunction "2_2") (pintype "passive"))
    )
    (net (code "77") (name "VCC_DIV") (class "Default")
      (node (ref "IC2") (pin "2") (pinfunction "PA03/I3/VREFA/AIN1_2") (pintype "bidirectional"))
      (node (ref "R3") (pin "2") (pinfunction "2_2") (pintype "passive"))
      (node (ref "R4") (pin "1") (pinfunction "1_1") (pintype "passive"))
    )
    (net (code "78") (name "VSW") (class "Default")
      (node (ref "IC3") (pin "43") (pinfunction "VSW_43") (pintype "power_in"))
    )
    (net (code "79") (name "unconnected-(IC2-PA04{slash}I4{slash}VREFB{slash}AIN2{slash}SERCOM0.2+0-Pad3)") (class "Default")
      (node (ref "IC2") (pin "3") (pinfunction "PA04/I4/VREFB/AIN2/SERCOM0.2+0_3") (pintype "bidirectional"))
    )
    (net (code "80") (name "unconnected-(IC2-PA06{slash}I6{slash}AIN4{slash}SERCOM0.0+2-Pad5)") (class "Default")
      (node (ref "IC2") (pin "5") (pinfunction "PA06/I6/AIN4/SERCOM0.0+2_5") (pintype "bidirectional"))
    )
    (net (code "81") (name "unconnected-(IC2-PA07{slash}I7{slash}AIN5{slash}SERCOM0.1+3-Pad6)") (class "Default")
      (node (ref "IC2") (pin "6") (pinfunction "PA07/I7/AIN5/SERCOM0.1+3_6") (pintype "bidirectional"))
    )
    (net (code "82") (name "unconnected-(IC2-PA14{slash}I2C{slash}AIN6{slash}SERCOM0.0-Pad11)") (class "Default")
      (node (ref "IC2") (pin "11") (pinfunction "PA14/I2C/AIN6/SERCOM0.0_11") (pintype "bidirectional"))
    )
    (net (code "83") (name "unconnected-(IC2-PA15{slash}I2C{slash}I1{slash}AIN7{slash}SERCOM0.1-Pad12)") (class "Default")
      (node (ref "IC2") (pin "12") (pinfunction "PA15/I2C/I1/AIN7/SERCOM0.1_12") (pintype "bidirectional"))
    )
    (net (code "84") (name "unconnected-(IC2-PA16{slash}I0{slash}SERCOM1.2-Pad13)") (class "Default")
      (node (ref "IC2") (pin "13") (pinfunction "PA16/I0/SERCOM1.2_13") (pintype "bidirectional"))
    )
    (net (code "85") (name "unconnected-(IC2-PA17{slash}I1{slash}SERCOM1.3-Pad14)") (class "Default")
      (node (ref "IC2") (pin "14") (pinfunction "PA17/I1/SERCOM1.3_14") (pintype "bidirectional"))
    )
    (net (code "86") (name "unconnected-(IC2-PA24{slash}I4{slash}SERCOM1.2-Pad21)") (class "Default")
      (node (ref "IC2") (pin "21") (pinfunction "PA24/I4/SERCOM1.2_21") (pintype "bidirectional"))
    )
    (net (code "87") (name "unconnected-(IC2-PA25{slash}I5{slash}SERCOM1.3-Pad22)") (class "Default")
      (node (ref "IC2") (pin "22") (pinfunction "PA25/I5/SERCOM1.3_22") (pintype "bidirectional"))
    )
    (net (code "88") (name "unconnected-(IC2-PA27{slash}I7-Pad17)") (class "Default")
      (node (ref "IC2") (pin "17") (pinfunction "PA27/I7_17") (pintype "bidirectional"))
    )
    (net (code "89") (name "unconnected-(IC3A-PA15{slash}I15{slash}SERCOM2+4.3-Pad24)") (class "Default")
      (node (ref "IC3") (pin "24") (pinfunction "PA15/I15/SERCOM2+4.3_24") (pintype "bidirectional"))
    )
    (net (code "90") (name "unconnected-(IC3A-PA18{slash}I2{slash}SERCOM1+3.2-Pad27)") (class "Default")
      (node (ref "IC3") (pin "27") (pinfunction "PA18/I2/SERCOM1+3.2_27") (pintype "bidirectional"))
    )
    (net (code "91") (name "unconnected-(IC3A-PA19{slash}I3{slash}SERCOM1+3.3-Pad28)") (class "Default")
      (node (ref "IC3") (pin "28") (pinfunction "PA19/I3/SERCOM1+3.3_28") (pintype "bidirectional"))
    )
    (net (code "92") (name "unconnected-(IC3A-PA20{slash}I4{slash}SERCOM3+5.2-Pad29)") (class "Default")
      (node (ref "IC3") (pin "29") (pinfunction "PA20/I4/SERCOM3+5.2_29") (pintype "bidirectional"))
    )
    (net (code "93") (name "unconnected-(IC3A-PA21{slash}I5{slash}SERCOM3+5.3-Pad30)") (class "Default")
      (node (ref "IC3") (pin "30") (pinfunction "PA21/I5/SERCOM3+5.3_30") (pintype "bidirectional"))
    )
    (net (code "94") (name "unconnected-(IC4-INT2-Pad9)") (class "Default")
      (node (ref "IC4") (pin "9") (pinfunction "INT2_9") (pintype "output"))
    )
    (net (code "95") (name "unconnected-(IC4-NC-Pad2)") (class "Default")
      (node (ref "IC4") (pin "2") (pinfunction "NC_2") (pintype "no_connect"))
    )
    (net (code "96") (name "unconnected-(IC4-NC-Pad3)") (class "Default")
      (node (ref "IC4") (pin "3") (pinfunction "NC_3") (pintype "no_connect"))
    )
    (net (code "97") (name "unconnected-(TFT1-TE-Pad19)") (class "Default")
      (node (ref "TFT1") (pin "19") (pinfunction "TE_19") (pintype "output"))
    )
    (net (code "98") (name "unconnected-(TFT2-TE-Pad19)") (class "Default")
      (node (ref "TFT2") (pin "19") (pinfunction "TE_19") (pintype "output"))
    )
    (net (code "99") (name "unconnected-(U4-P4-Pad4)") (class "Default")
      (node (ref "U4") (pin "4") (pinfunction "P4_4") (pintype "bidirectional"))
    )
    (net (code "100") (name "unconnected-(U5-NC-Pad2)") (class "Default")
      (node (ref "U5") (pin "2") (pinfunction "NC_2") (pintype "no_connect"))
    )
    (net (code "101") (name "unconnected-(U6-P4-Pad4)") (class "Default")
      (node (ref "U6") (pin "4") (pinfunction "P4_4") (pintype "bidirectional"))
    )
    (net (code "102") (name "unconnected-(X3-PadID)") (class "Default")
      (node (ref "X3") (pin "ID") (pinfunction "ID_ID") (pintype "bidirectional"))
    )
    (net (code "103") (name "~{RESET}") (class "Default")
      (node (ref "C11") (pin "2") (pinfunction "2_2") (pintype "passive"))
      (node (ref "IC3") (pin "40") (pinfunction "/RESET_40") (pintype "bidirectional"))
      (node (ref "R19") (pin "5") (pinfunction "2_5") (pintype "passive"))
      (node (ref "SW2") (pin "1") (pinfunction "P_1") (pintype "passive"))
      (node (ref "TP8") (pin "P$1") (pinfunction "P$1_P$1") (pintype "bidirectional"))
    )
  )
)
